# timer_main.net
KiCad netlist of a schematic drawn in Altium Designer
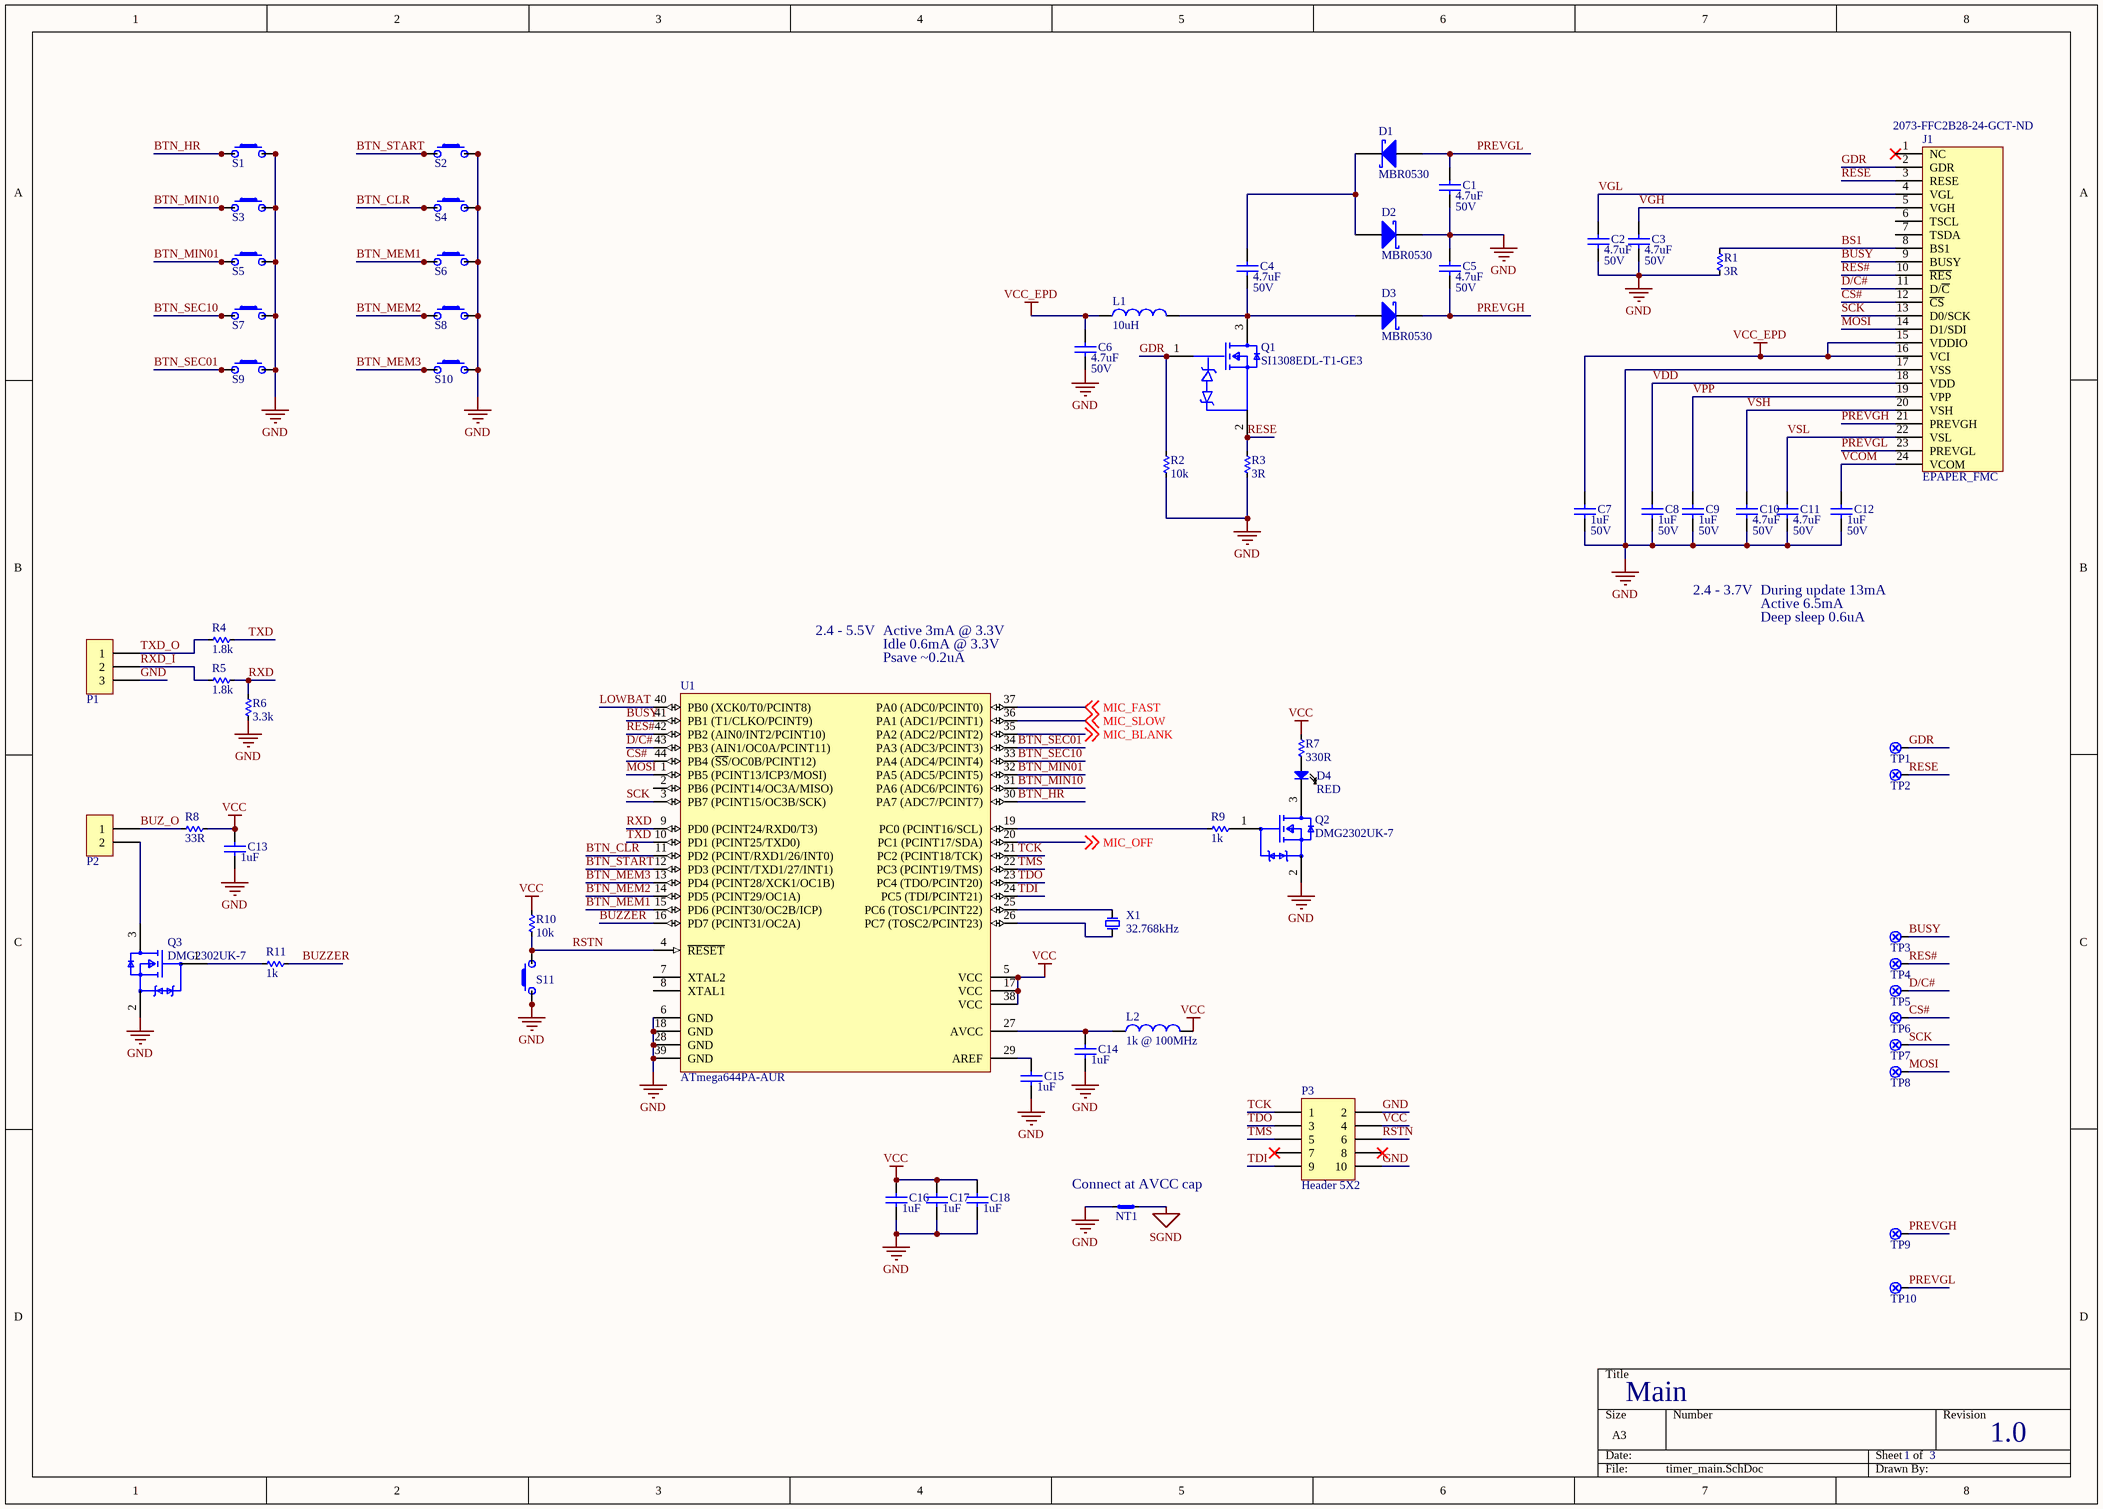
[diagram p0: timer_main.SchDoc]

(export (version "E")
  (design (tool "Eeschema 10.0.6"))
  (components
    (comp (ref "C1")
      (value "4.7uF")
      (footprint "C0805/2012")
      (description "Capacitor")
      (fields (field (name "TOLERANCE") "x%") (field (name "VOLTAGE") "50V") (field (name "Comment") "CAP"))
      (libsource (lib "ZMPlib") (part "CAP"))
    )
    (comp (ref "C2")
      (value "4.7uF")
      (footprint "C0805/2012")
      (description "Capacitor")
      (fields (field (name "TOLERANCE") "x%") (field (name "VOLTAGE") "50V") (field (name "Comment") "CAP"))
      (libsource (lib "ZMPlib") (part "CAP"))
    )
    (comp (ref "C3")
      (value "4.7uF")
      (footprint "C0805/2012")
      (description "Capacitor")
      (fields (field (name "TOLERANCE") "x%") (field (name "VOLTAGE") "50V") (field (name "Comment") "CAP"))
      (libsource (lib "ZMPlib") (part "CAP"))
    )
    (comp (ref "C4")
      (value "4.7uF")
      (footprint "C0805/2012")
      (description "Capacitor")
      (fields (field (name "TOLERANCE") "x%") (field (name "VOLTAGE") "50V") (field (name "Comment") "CAP"))
      (libsource (lib "ZMPlib") (part "CAP"))
    )
    (comp (ref "C5")
      (value "4.7uF")
      (footprint "C0805/2012")
      (description "Capacitor")
      (fields (field (name "TOLERANCE") "x%") (field (name "VOLTAGE") "50V") (field (name "Comment") "CAP"))
      (libsource (lib "ZMPlib") (part "CAP"))
    )
    (comp (ref "C6")
      (value "4.7uF")
      (footprint "C0805/2012")
      (description "Capacitor")
      (fields (field (name "TOLERANCE") "x%") (field (name "VOLTAGE") "50V") (field (name "Comment") "CAP"))
      (libsource (lib "ZMPlib") (part "CAP"))
    )
    (comp (ref "C7")
      (value "1uF")
      (footprint "C0603/1608")
      (description "Capacitor")
      (fields (field (name "TOLERANCE") "x%") (field (name "VOLTAGE") "50V") (field (name "Comment") "CAP"))
      (libsource (lib "ZMPlib") (part "CAP"))
    )
    (comp (ref "C8")
      (value "1uF")
      (footprint "C0603/1608")
      (description "Capacitor")
      (fields (field (name "TOLERANCE") "x%") (field (name "VOLTAGE") "50V") (field (name "Comment") "CAP"))
      (libsource (lib "ZMPlib") (part "CAP"))
    )
    (comp (ref "C9")
      (value "1uF")
      (footprint "C0603/1608")
      (description "Capacitor")
      (fields (field (name "TOLERANCE") "x%") (field (name "VOLTAGE") "50V") (field (name "Comment") "CAP"))
      (libsource (lib "ZMPlib") (part "CAP"))
    )
    (comp (ref "C10")
      (value "4.7uF")
      (footprint "C0805/2012")
      (description "Capacitor")
      (fields (field (name "TOLERANCE") "x%") (field (name "VOLTAGE") "50V") (field (name "Comment") "CAP"))
      (libsource (lib "ZMPlib") (part "CAP"))
    )
    (comp (ref "C11")
      (value "4.7uF")
      (footprint "C0805/2012")
      (description "Capacitor")
      (fields (field (name "TOLERANCE") "x%") (field (name "VOLTAGE") "50V") (field (name "Comment") "CAP"))
      (libsource (lib "ZMPlib") (part "CAP"))
    )
    (comp (ref "C12")
      (value "1uF")
      (footprint "C0603/1608")
      (description "Capacitor")
      (fields (field (name "TOLERANCE") "x%") (field (name "VOLTAGE") "50V") (field (name "Comment") "CAP"))
      (libsource (lib "ZMPlib") (part "CAP"))
    )
    (comp (ref "C13")
      (value "1uF")
      (footprint "C0603/1608")
      (description "Capacitor")
      (fields (field (name "TOLERANCE") "x%") (field (name "VOLTAGE") "6.3V"))
      (libsource (lib "ZMPlib") (part "CAP"))
    )
    (comp (ref "C14")
      (value "1uF")
      (footprint "C0603/1608")
      (description "Capacitor")
      (fields (field (name "TOLERANCE") "x%") (field (name "VOLTAGE") "6.3V"))
      (libsource (lib "ZMPlib") (part "CAP"))
    )
    (comp (ref "C15")
      (value "1uF")
      (footprint "C0603/1608")
      (description "Capacitor")
      (fields (field (name "TOLERANCE") "x%") (field (name "VOLTAGE") "6.3V"))
      (libsource (lib "ZMPlib") (part "CAP"))
    )
    (comp (ref "C16")
      (value "1uF")
      (footprint "C0603/1608")
      (description "Capacitor")
      (fields (field (name "TOLERANCE") "x%") (field (name "VOLTAGE") "6.3V"))
      (libsource (lib "ZMPlib") (part "CAP"))
    )
    (comp (ref "C17")
      (value "1uF")
      (footprint "C0603/1608")
      (description "Capacitor")
      (fields (field (name "TOLERANCE") "x%") (field (name "VOLTAGE") "6.3V"))
      (libsource (lib "ZMPlib") (part "CAP"))
    )
    (comp (ref "C18")
      (value "1uF")
      (footprint "C0603/1608")
      (description "Capacitor")
      (fields (field (name "TOLERANCE") "x%") (field (name "VOLTAGE") "6.3V"))
      (libsource (lib "ZMPlib") (part "CAP"))
    )
    (comp (ref "D1")
      (value "MBR0530")
      (footprint "FAIR-SOD123-2_V")
      (description "Diode Schottky 30V 0.5A 2-Pin SOD-123 T/R")
      (fields (field (name "MANUFACTURER") "Fairchild"))
      (libsource (lib "Altium Content Vault") (part "DSKY-AK-2"))
    )
    (comp (ref "D2")
      (value "MBR0530")
      (footprint "FAIR-SOD123-2_V")
      (description "Diode Schottky 30V 0.5A 2-Pin SOD-123 T/R")
      (fields (field (name "MANUFACTURER") "Fairchild"))
      (libsource (lib "Altium Content Vault") (part "DSKY-AK-2"))
    )
    (comp (ref "D3")
      (value "MBR0530")
      (footprint "FAIR-SOD123-2_V")
      (description "Diode Schottky 30V 0.5A 2-Pin SOD-123 T/R")
      (fields (field (name "MANUFACTURER") "Fairchild"))
      (libsource (lib "Altium Content Vault") (part "DSKY-AK-2"))
    )
    (comp (ref "D4")
      (value "RED")
      (footprint "0603/1608_P")
      (description "LED")
      (libsource (lib "ZMPlib") (part "LED"))
    )
    (comp (ref "J1")
      (value "EPAPER_FMC")
      (footprint "FFC2B28-24-G REV")
      (description "FMC connector for epaper display from Dailan Good Display")
      (fields (field (name "SUPPLIER PART NUMBER 1") "2073-FFC2B28-24-GCT-ND"))
      (libsource (lib "ZMPlib") (part "EPAPER_FMC"))
    )
    (comp (ref "L1")
      (value "10uH")
      (footprint "IND4x4mm")
      (description "Inductor")
      (fields (field (name "Comment") "IND"))
      (libsource (lib "ZMPlib") (part "IND"))
    )
    (comp (ref "L2")
      (value "1k @ 100MHz")
      (footprint "R0603/1608")
      (description "Inductor")
      (fields (field (name "Comment") "FERRITE"))
      (libsource (lib "ZMPlib") (part "IND"))
    )
    (comp (ref "NT1")
      (value "NET_TIE2")
      (footprint "NT2_0.5mm")
      (description "Link between nets")
      (libsource (lib "ZMPlib") (part "NET_TIE2"))
    )
    (comp (ref "P1")
      (value "SIL3")
      (footprint "PINS-3")
      (description "SIL package, 3 pins")
      (libsource (lib "ZMPlib") (part "SIL3"))
    )
    (comp (ref "P2")
      (value "SIL2")
      (footprint "PINS-2")
      (description "SIL package, 2 pins")
      (libsource (lib "ZMPlib") (part "SIL2"))
    )
    (comp (ref "P3")
      (value "Header 5X2")
      (footprint "HDR2X5")
      (description "Header, 5-Pin, Dual row")
      (fields (field (name "PUBLISHER") "Altium Limited"))
      (libsource (lib "Miscellaneous Connectors") (part "Header 5X2"))
    )
    (comp (ref "Q1")
      (value "SI1308EDL-T1-GE3")
      (footprint "FP-S-03946-MFG")
      (description "MOSFET N-CH 30V 1.4A SC-70-3")
      (fields
        (field (name "OCTOPART") "https://octopart.com/si1308edl-t1-ge3-vishay-45284459")
        (field (name "MANUFACTURER") "Vishay")
      )
      (libsource (lib "Altium Content Vault") (part "b3bb3e825a9d846c0de22584db20962"))
    )
    (comp (ref "Q2")
      (value "DMG2302UK-7")
      (footprint "FP-SOT23-MFG")
      (description "MOSFET N-CH 20V 2.8A SOT23")
      (fields
        (field (name "OCTOPART") "https://octopart.com/dmg2302uk-7-diodes+inc.-73850182")
        (field (name "MANUFACTURER") "Diodes Inc.")
      )
      (libsource (lib "Altium Content Vault") (part "87c0c04a04979492222792dd46c39c9"))
    )
    (comp (ref "Q3")
      (value "DMG2302UK-7")
      (footprint "FP-SOT23-MFG")
      (description "MOSFET N-CH 20V 2.8A SOT23")
      (fields
        (field (name "OCTOPART") "https://octopart.com/dmg2302uk-7-diodes+inc.-73850182")
        (field (name "MANUFACTURER") "Diodes Inc.")
      )
      (libsource (lib "Altium Content Vault") (part "87c0c04a04979492222792dd46c39c9"))
    )
    (comp (ref "R1")
      (value "3R")
      (footprint "R0603/1608")
      (description "Resistor")
      (fields (field (name "TOLERANCE") "x%") (field (name "Comment") "RES"))
      (libsource (lib "ZMPlib") (part "RES"))
    )
    (comp (ref "R2")
      (value "10k")
      (footprint "R0603/1608")
      (description "Resistor")
      (fields (field (name "TOLERANCE") "x%") (field (name "Comment") "RES"))
      (libsource (lib "ZMPlib") (part "RES"))
    )
    (comp (ref "R3")
      (value "3R")
      (footprint "R0603/1608")
      (description "Resistor")
      (fields (field (name "TOLERANCE") "x%") (field (name "Comment") "RES"))
      (libsource (lib "ZMPlib") (part "RES"))
    )
    (comp (ref "R4")
      (value "1.8k")
      (footprint "R0603/1608")
      (description "Resistor")
      (fields (field (name "TOLERANCE") "x%") (field (name "Comment") "RES"))
      (libsource (lib "ZMPlib") (part "RES"))
    )
    (comp (ref "R5")
      (value "1.8k")
      (footprint "R0603/1608")
      (description "Resistor")
      (fields (field (name "TOLERANCE") "x%") (field (name "Comment") "RES"))
      (libsource (lib "ZMPlib") (part "RES"))
    )
    (comp (ref "R6")
      (value "3.3k")
      (footprint "R0603/1608")
      (description "Resistor")
      (fields (field (name "TOLERANCE") "x%") (field (name "Comment") "RES"))
      (libsource (lib "ZMPlib") (part "RES"))
    )
    (comp (ref "R7")
      (value "330R")
      (footprint "R0603/1608")
      (description "Resistor")
      (fields (field (name "TOLERANCE") "x%") (field (name "Comment") "RES"))
      (libsource (lib "ZMPlib") (part "RES"))
    )
    (comp (ref "R8")
      (value "33R")
      (footprint "R0603/1608")
      (description "Resistor")
      (fields (field (name "TOLERANCE") "x%") (field (name "Comment") "RES"))
      (libsource (lib "ZMPlib") (part "RES"))
    )
    (comp (ref "R9")
      (value "1k")
      (footprint "R0603/1608")
      (description "Resistor")
      (fields (field (name "TOLERANCE") "x%") (field (name "Comment") "RES"))
      (libsource (lib "ZMPlib") (part "RES"))
    )
    (comp (ref "R10")
      (value "10k")
      (footprint "R0603/1608")
      (description "Resistor")
      (fields (field (name "TOLERANCE") "x%") (field (name "Comment") "RES"))
      (libsource (lib "ZMPlib") (part "RES"))
    )
    (comp (ref "R11")
      (value "1k")
      (footprint "R0603/1608")
      (description "Resistor")
      (fields (field (name "TOLERANCE") "x%") (field (name "Comment") "RES"))
      (libsource (lib "ZMPlib") (part "RES"))
    )
    (comp (ref "S1")
      (value "SW")
      (footprint "SW-PTS645-SMT")
      (description "Switch")
      (libsource (lib "ZMPlib") (part "SW-PB"))
    )
    (comp (ref "S2")
      (value "SW")
      (footprint "SW-PTS645-SMT")
      (description "Switch")
      (libsource (lib "ZMPlib") (part "SW-PB"))
    )
    (comp (ref "S3")
      (value "SW")
      (footprint "SW-PTS645-SMT")
      (description "Switch")
      (libsource (lib "ZMPlib") (part "SW-PB"))
    )
    (comp (ref "S4")
      (value "SW")
      (footprint "SW-PTS645-SMT")
      (description "Switch")
      (libsource (lib "ZMPlib") (part "SW-PB"))
    )
    (comp (ref "S5")
      (value "SW")
      (footprint "SW-PTS645-SMT")
      (description "Switch")
      (libsource (lib "ZMPlib") (part "SW-PB"))
    )
    (comp (ref "S6")
      (value "SW")
      (footprint "SW-PTS645-SMT")
      (description "Switch")
      (libsource (lib "ZMPlib") (part "SW-PB"))
    )
    (comp (ref "S7")
      (value "SW")
      (footprint "SW-PTS645-SMT")
      (description "Switch")
      (libsource (lib "ZMPlib") (part "SW-PB"))
    )
    (comp (ref "S8")
      (value "SW")
      (footprint "SW-PTS645-SMT")
      (description "Switch")
      (libsource (lib "ZMPlib") (part "SW-PB"))
    )
    (comp (ref "S9")
      (value "SW")
      (footprint "SW-PTS645-SMT")
      (description "Switch")
      (libsource (lib "ZMPlib") (part "SW-PB"))
    )
    (comp (ref "S10")
      (value "SW")
      (footprint "SW-PTS645-SMT")
      (description "Switch")
      (libsource (lib "ZMPlib") (part "SW-PB"))
    )
    (comp (ref "S11")
      (value "SW")
      (footprint "SW-PTS645-SMT")
      (description "Switch")
      (libsource (lib "ZMPlib") (part "SW-PB"))
    )
    (comp (ref "TP1")
      (value "TP")
      (footprint "TP-1.0")
      (description "Test point")
      (libsource (lib "ZMPlib") (part "TP"))
    )
    (comp (ref "TP2")
      (value "TP")
      (footprint "TP-1.0")
      (description "Test point")
      (libsource (lib "ZMPlib") (part "TP"))
    )
    (comp (ref "TP3")
      (value "TP")
      (footprint "TP-1.0")
      (description "Test point")
      (libsource (lib "ZMPlib") (part "TP"))
    )
    (comp (ref "TP4")
      (value "TP")
      (footprint "TP-1.0")
      (description "Test point")
      (libsource (lib "ZMPlib") (part "TP"))
    )
    (comp (ref "TP5")
      (value "TP")
      (footprint "TP-1.0")
      (description "Test point")
      (libsource (lib "ZMPlib") (part "TP"))
    )
    (comp (ref "TP6")
      (value "TP")
      (footprint "TP-1.0")
      (description "Test point")
      (libsource (lib "ZMPlib") (part "TP"))
    )
    (comp (ref "TP7")
      (value "TP")
      (footprint "TP-1.0")
      (description "Test point")
      (libsource (lib "ZMPlib") (part "TP"))
    )
    (comp (ref "TP8")
      (value "TP")
      (footprint "TP-1.0")
      (description "Test point")
      (libsource (lib "ZMPlib") (part "TP"))
    )
    (comp (ref "TP9")
      (value "TP")
      (footprint "TP-1.0")
      (description "Test point")
      (libsource (lib "ZMPlib") (part "TP"))
    )
    (comp (ref "TP10")
      (value "TP")
      (footprint "TP-1.0")
      (description "Test point")
      (libsource (lib "ZMPlib") (part "TP"))
    )
    (comp (ref "U1")
      (value "ATmega644PA-AUR")
      (footprint "44A_N")
      (libsource (lib "Altium Content Vault") (part "MC-8B-ATM128-SQ44"))
    )
    (comp (ref "X1")
      (value "32.768kHz")
      (footprint "CMR200T")
      (description "Crystal")
      (fields (field (name "Comment") "XTAL"))
      (libsource (lib "ZMPlib") (part "XTAL"))
    )
  )
  (nets
    (net (code "1") (name "/BS1") (class "Default")
      (node (ref "J1") (pin "8") (pinfunction "BS1_8") (pintype "passive"))
      (node (ref "R1") (pin "1") (pinfunction "1_1") (pintype "passive"))
    )
    (net (code "2") (name "/BTN_CLR") (class "Default")
      (node (ref "S4") (pin "1") (pinfunction "1_1") (pintype "passive"))
      (node (ref "S4") (pin "2") (pinfunction "2_2") (pintype "passive"))
      (node (ref "U1") (pin "11") (pinfunction "PD2_(PCINT/RXD1/26/INT0)_11") (pintype "bidirectional"))
    )
    (net (code "3") (name "/BTN_HR") (class "Default")
      (node (ref "S1") (pin "1") (pinfunction "1_1") (pintype "passive"))
      (node (ref "S1") (pin "2") (pinfunction "2_2") (pintype "passive"))
      (node (ref "U1") (pin "30") (pinfunction "PA7_(ADC7/PCINT7)_30") (pintype "bidirectional"))
    )
    (net (code "4") (name "/BTN_MEM1") (class "Default")
      (node (ref "S6") (pin "1") (pinfunction "1_1") (pintype "passive"))
      (node (ref "S6") (pin "2") (pinfunction "2_2") (pintype "passive"))
      (node (ref "U1") (pin "15") (pinfunction "PD6_(PCINT30/OC2B/ICP)_15") (pintype "bidirectional"))
    )
    (net (code "5") (name "/BTN_MEM2") (class "Default")
      (node (ref "S8") (pin "1") (pinfunction "1_1") (pintype "passive"))
      (node (ref "S8") (pin "2") (pinfunction "2_2") (pintype "passive"))
      (node (ref "U1") (pin "14") (pinfunction "PD5_(PCINT29/OC1A)_14") (pintype "bidirectional"))
    )
    (net (code "6") (name "/BTN_MEM3") (class "Default")
      (node (ref "S10") (pin "1") (pinfunction "1_1") (pintype "passive"))
      (node (ref "S10") (pin "2") (pinfunction "2_2") (pintype "passive"))
      (node (ref "U1") (pin "13") (pinfunction "PD4_(PCINT28/XCK1/OC1B)_13") (pintype "bidirectional"))
    )
    (net (code "7") (name "/BTN_MIN01") (class "Default")
      (node (ref "S5") (pin "1") (pinfunction "1_1") (pintype "passive"))
      (node (ref "S5") (pin "2") (pinfunction "2_2") (pintype "passive"))
      (node (ref "U1") (pin "32") (pinfunction "PA5_(ADC5/PCINT5)_32") (pintype "bidirectional"))
    )
    (net (code "8") (name "/BTN_MIN10") (class "Default")
      (node (ref "S3") (pin "1") (pinfunction "1_1") (pintype "passive"))
      (node (ref "S3") (pin "2") (pinfunction "2_2") (pintype "passive"))
      (node (ref "U1") (pin "31") (pinfunction "PA6_(ADC6/PCINT6)_31") (pintype "bidirectional"))
    )
    (net (code "9") (name "/BTN_SEC01") (class "Default")
      (node (ref "S9") (pin "1") (pinfunction "1_1") (pintype "passive"))
      (node (ref "S9") (pin "2") (pinfunction "2_2") (pintype "passive"))
      (node (ref "U1") (pin "34") (pinfunction "PA3_(ADC3/PCINT3)_34") (pintype "bidirectional"))
    )
    (net (code "10") (name "/BTN_SEC10") (class "Default")
      (node (ref "S7") (pin "1") (pinfunction "1_1") (pintype "passive"))
      (node (ref "S7") (pin "2") (pinfunction "2_2") (pintype "passive"))
      (node (ref "U1") (pin "33") (pinfunction "PA4_(ADC4/PCINT4)_33") (pintype "bidirectional"))
    )
    (net (code "11") (name "/BTN_START") (class "Default")
      (node (ref "S2") (pin "1") (pinfunction "1_1") (pintype "passive"))
      (node (ref "S2") (pin "2") (pinfunction "2_2") (pintype "passive"))
      (node (ref "U1") (pin "12") (pinfunction "PD3_(PCINT/TXD1/27/INT1)_12") (pintype "bidirectional"))
    )
    (net (code "12") (name "/BUSY") (class "Default")
      (node (ref "J1") (pin "9") (pinfunction "BUSY_9") (pintype "passive"))
      (node (ref "TP3") (pin "0") (pinfunction "0_0") (pintype "passive"))
      (node (ref "U1") (pin "41") (pinfunction "PB1_(T1/CLKO/PCINT9)_41") (pintype "bidirectional"))
    )
    (net (code "13") (name "/BUZZER") (class "Default")
      (node (ref "R11") (pin "2") (pinfunction "2_2") (pintype "passive"))
      (node (ref "U1") (pin "16") (pinfunction "PD7_(PCINT31/OC2A)_16") (pintype "bidirectional"))
    )
    (net (code "14") (name "/BUZ_O") (class "Default")
      (node (ref "P2") (pin "1") (pinfunction "1_1") (pintype "passive"))
      (node (ref "R8") (pin "1") (pinfunction "1_1") (pintype "passive"))
    )
    (net (code "15") (name "/CS#") (class "Default")
      (node (ref "J1") (pin "12") (pinfunction "~{CS}_12") (pintype "passive"))
      (node (ref "TP6") (pin "0") (pinfunction "0_0") (pintype "passive"))
      (node (ref "U1") (pin "44") (pinfunction "PB4_(~{SS}/OC0B/PCINT12)_44") (pintype "bidirectional"))
    )
    (net (code "16") (name "/D{slash}C#") (class "Default")
      (node (ref "J1") (pin "11") (pinfunction "D/~{C}_11") (pintype "passive"))
      (node (ref "TP5") (pin "0") (pinfunction "0_0") (pintype "passive"))
      (node (ref "U1") (pin "43") (pinfunction "PB3_(AIN1/OC0A/PCINT11)_43") (pintype "bidirectional"))
    )
    (net (code "17") (name "/GDR") (class "Default")
      (node (ref "J1") (pin "2") (pinfunction "GDR_2") (pintype "passive"))
      (node (ref "Q1") (pin "1") (pinfunction "G_1") (pintype "passive"))
      (node (ref "R2") (pin "1") (pinfunction "1_1") (pintype "passive"))
      (node (ref "TP1") (pin "0") (pinfunction "0_0") (pintype "passive"))
    )
    (net (code "18") (name "/LOWBAT") (class "Default")
      (node (ref "U1") (pin "40") (pinfunction "PB0_(XCK0/T0/PCINT8)_40") (pintype "bidirectional"))
    )
    (net (code "19") (name "/MOSI") (class "Default")
      (node (ref "J1") (pin "14") (pinfunction "D1/SDI_14") (pintype "passive"))
      (node (ref "TP8") (pin "0") (pinfunction "0_0") (pintype "passive"))
      (node (ref "U1") (pin "1") (pinfunction "PB5_(PCINT13/ICP3/MOSI)_1") (pintype "bidirectional"))
    )
    (net (code "20") (name "/PREVGH") (class "Default")
      (node (ref "C5") (pin "1") (pinfunction "1_1") (pintype "passive"))
      (node (ref "D3") (pin "2") (pinfunction "K_2") (pintype "passive"))
      (node (ref "J1") (pin "21") (pinfunction "PREVGH_21") (pintype "passive"))
      (node (ref "TP9") (pin "0") (pinfunction "0_0") (pintype "passive"))
    )
    (net (code "21") (name "/PREVGL") (class "Default")
      (node (ref "C1") (pin "2") (pinfunction "2_2") (pintype "passive"))
      (node (ref "D1") (pin "1") (pinfunction "A_1") (pintype "passive"))
      (node (ref "J1") (pin "23") (pinfunction "PREVGL_23") (pintype "passive"))
      (node (ref "TP10") (pin "0") (pinfunction "0_0") (pintype "passive"))
    )
    (net (code "22") (name "/RES#") (class "Default")
      (node (ref "J1") (pin "10") (pinfunction "~{RES}_10") (pintype "passive"))
      (node (ref "TP4") (pin "0") (pinfunction "0_0") (pintype "passive"))
      (node (ref "U1") (pin "42") (pinfunction "PB2_(AIN0/INT2/PCINT10)_42") (pintype "bidirectional"))
    )
    (net (code "23") (name "/RESE") (class "Default")
      (node (ref "J1") (pin "3") (pinfunction "RESE_3") (pintype "passive"))
      (node (ref "Q1") (pin "2") (pinfunction "S_2") (pintype "passive"))
      (node (ref "R3") (pin "1") (pinfunction "1_1") (pintype "passive"))
      (node (ref "TP2") (pin "0") (pinfunction "0_0") (pintype "passive"))
    )
    (net (code "24") (name "/RSTN") (class "Default")
      (node (ref "P3") (pin "6") (pinfunction "6_6") (pintype "passive"))
      (node (ref "R10") (pin "2") (pinfunction "2_2") (pintype "passive"))
      (node (ref "S11") (pin "3") (pinfunction "3_3") (pintype "passive"))
      (node (ref "S11") (pin "4") (pinfunction "4_4") (pintype "passive"))
      (node (ref "U1") (pin "4") (pinfunction "~{RESET}_4") (pintype "input"))
    )
    (net (code "25") (name "/RXD") (class "Default")
      (node (ref "R5") (pin "2") (pinfunction "2_2") (pintype "passive"))
      (node (ref "R6") (pin "1") (pinfunction "1_1") (pintype "passive"))
      (node (ref "U1") (pin "9") (pinfunction "PD0_(PCINT24/RXD0/T3)_9") (pintype "bidirectional"))
    )
    (net (code "26") (name "/RXD_I") (class "Default")
      (node (ref "P1") (pin "2") (pinfunction "2_2") (pintype "passive"))
      (node (ref "R5") (pin "1") (pinfunction "1_1") (pintype "passive"))
    )
    (net (code "27") (name "/SCK") (class "Default")
      (node (ref "J1") (pin "13") (pinfunction "D0/SCK_13") (pintype "passive"))
      (node (ref "TP7") (pin "0") (pinfunction "0_0") (pintype "passive"))
      (node (ref "U1") (pin "3") (pinfunction "PB7_(PCINT15/OC3B/SCK)_3") (pintype "bidirectional"))
    )
    (net (code "28") (name "/TCK") (class "Default")
      (node (ref "P3") (pin "1") (pinfunction "1_1") (pintype "passive"))
      (node (ref "U1") (pin "21") (pinfunction "PC2_(PCINT18/TCK)_21") (pintype "bidirectional"))
    )
    (net (code "29") (name "/TDI") (class "Default")
      (node (ref "P3") (pin "9") (pinfunction "9_9") (pintype "passive"))
      (node (ref "U1") (pin "24") (pinfunction "PC5_(TDI/PCINT21)_24") (pintype "bidirectional"))
    )
    (net (code "30") (name "/TDO") (class "Default")
      (node (ref "P3") (pin "3") (pinfunction "3_3") (pintype "passive"))
      (node (ref "U1") (pin "23") (pinfunction "PC4_(TDO/PCINT20)_23") (pintype "bidirectional"))
    )
    (net (code "31") (name "/TMS") (class "Default")
      (node (ref "P3") (pin "5") (pinfunction "5_5") (pintype "passive"))
      (node (ref "U1") (pin "22") (pinfunction "PC3_(PCINT19/TMS)_22") (pintype "bidirectional"))
    )
    (net (code "32") (name "/TXD") (class "Default")
      (node (ref "R4") (pin "2") (pinfunction "2_2") (pintype "passive"))
      (node (ref "U1") (pin "10") (pinfunction "PD1_(PCINT25/TXD0)_10") (pintype "bidirectional"))
    )
    (net (code "33") (name "/TXD_O") (class "Default")
      (node (ref "P1") (pin "1") (pinfunction "1_1") (pintype "passive"))
      (node (ref "R4") (pin "1") (pinfunction "1_1") (pintype "passive"))
    )
    (net (code "34") (name "/VCOM") (class "Default")
      (node (ref "C12") (pin "2") (pinfunction "2_2") (pintype "passive"))
      (node (ref "J1") (pin "24") (pinfunction "VCOM_24") (pintype "passive"))
    )
    (net (code "35") (name "/VDD") (class "Default")
      (node (ref "C8") (pin "2") (pinfunction "2_2") (pintype "passive"))
      (node (ref "J1") (pin "18") (pinfunction "VDD_18") (pintype "passive"))
    )
    (net (code "36") (name "/VGH") (class "Default")
      (node (ref "C3") (pin "2") (pinfunction "2_2") (pintype "passive"))
      (node (ref "J1") (pin "5") (pinfunction "VGH_5") (pintype "passive"))
    )
    (net (code "37") (name "/VGL") (class "Default")
      (node (ref "C2") (pin "2") (pinfunction "2_2") (pintype "passive"))
      (node (ref "J1") (pin "4") (pinfunction "VGL_4") (pintype "passive"))
    )
    (net (code "38") (name "/VPP") (class "Default")
      (node (ref "C9") (pin "2") (pinfunction "2_2") (pintype "passive"))
      (node (ref "J1") (pin "19") (pinfunction "VPP_19") (pintype "passive"))
    )
    (net (code "39") (name "/VSH") (class "Default")
      (node (ref "C10") (pin "2") (pinfunction "2_2") (pintype "passive"))
      (node (ref "J1") (pin "20") (pinfunction "VSH_20") (pintype "passive"))
    )
    (net (code "40") (name "/VSL") (class "Default")
      (node (ref "C11") (pin "2") (pinfunction "2_2") (pintype "passive"))
      (node (ref "J1") (pin "22") (pinfunction "VSL_22") (pintype "passive"))
    )
    (net (code "41") (name "GND") (class "Default")
      (node (ref "C1") (pin "1") (pinfunction "1_1") (pintype "passive"))
      (node (ref "C10") (pin "1") (pinfunction "1_1") (pintype "passive"))
      (node (ref "C11") (pin "1") (pinfunction "1_1") (pintype "passive"))
      (node (ref "C12") (pin "1") (pinfunction "1_1") (pintype "passive"))
      (node (ref "C13") (pin "1") (pinfunction "1_1") (pintype "passive"))
      (node (ref "C14") (pin "1") (pinfunction "1_1") (pintype "passive"))
      (node (ref "C15") (pin "1") (pinfunction "1_1") (pintype "passive"))
      (node (ref "C16") (pin "1") (pinfunction "1_1") (pintype "passive"))
      (node (ref "C17") (pin "1") (pinfunction "1_1") (pintype "passive"))
      (node (ref "C18") (pin "1") (pinfunction "1_1") (pintype "passive"))
      (node (ref "C2") (pin "1") (pinfunction "1_1") (pintype "passive"))
      (node (ref "C3") (pin "1") (pinfunction "1_1") (pintype "passive"))
      (node (ref "C5") (pin "2") (pinfunction "2_2") (pintype "passive"))
      (node (ref "C6") (pin "1") (pinfunction "1_1") (pintype "passive"))
      (node (ref "C7") (pin "1") (pinfunction "1_1") (pintype "passive"))
      (node (ref "C8") (pin "1") (pinfunction "1_1") (pintype "passive"))
      (node (ref "C9") (pin "1") (pinfunction "1_1") (pintype "passive"))
      (node (ref "D2") (pin "2") (pinfunction "K_2") (pintype "passive"))
      (node (ref "J1") (pin "17") (pinfunction "VSS_17") (pintype "passive"))
      (node (ref "NT1") (pin "1") (pinfunction "1_1") (pintype "passive"))
      (node (ref "P1") (pin "3") (pinfunction "3_3") (pintype "passive"))
      (node (ref "P3") (pin "10") (pinfunction "10_10") (pintype "passive"))
      (node (ref "P3") (pin "2") (pinfunction "2_2") (pintype "passive"))
      (node (ref "Q2") (pin "2") (pinfunction "S_2") (pintype "passive"))
      (node (ref "Q3") (pin "2") (pinfunction "S_2") (pintype "passive"))
      (node (ref "R1") (pin "2") (pinfunction "2_2") (pintype "passive"))
      (node (ref "R2") (pin "2") (pinfunction "2_2") (pintype "passive"))
      (node (ref "R3") (pin "2") (pinfunction "2_2") (pintype "passive"))
      (node (ref "R6") (pin "2") (pinfunction "2_2") (pintype "passive"))
      (node (ref "S1") (pin "3") (pinfunction "3_3") (pintype "passive"))
      (node (ref "S1") (pin "4") (pinfunction "4_4") (pintype "passive"))
      (node (ref "S10") (pin "3") (pinfunction "3_3") (pintype "passive"))
      (node (ref "S10") (pin "4") (pinfunction "4_4") (pintype "passive"))
      (node (ref "S11") (pin "1") (pinfunction "1_1") (pintype "passive"))
      (node (ref "S11") (pin "2") (pinfunction "2_2") (pintype "passive"))
      (node (ref "S2") (pin "3") (pinfunction "3_3") (pintype "passive"))
      (node (ref "S2") (pin "4") (pinfunction "4_4") (pintype "passive"))
      (node (ref "S3") (pin "3") (pinfunction "3_3") (pintype "passive"))
      (node (ref "S3") (pin "4") (pinfunction "4_4") (pintype "passive"))
      (node (ref "S4") (pin "3") (pinfunction "3_3") (pintype "passive"))
      (node (ref "S4") (pin "4") (pinfunction "4_4") (pintype "passive"))
      (node (ref "S5") (pin "3") (pinfunction "3_3") (pintype "passive"))
      (node (ref "S5") (pin "4") (pinfunction "4_4") (pintype "passive"))
      (node (ref "S6") (pin "3") (pinfunction "3_3") (pintype "passive"))
      (node (ref "S6") (pin "4") (pinfunction "4_4") (pintype "passive"))
      (node (ref "S7") (pin "3") (pinfunction "3_3") (pintype "passive"))
      (node (ref "S7") (pin "4") (pinfunction "4_4") (pintype "passive"))
      (node (ref "S8") (pin "3") (pinfunction "3_3") (pintype "passive"))
      (node (ref "S8") (pin "4") (pinfunction "4_4") (pintype "passive"))
      (node (ref "S9") (pin "3") (pinfunction "3_3") (pintype "passive"))
      (node (ref "S9") (pin "4") (pinfunction "4_4") (pintype "passive"))
      (node (ref "U1") (pin "18") (pinfunction "GND_18") (pintype "power_in"))
      (node (ref "U1") (pin "28") (pinfunction "GND_28") (pintype "power_in"))
      (node (ref "U1") (pin "39") (pinfunction "GND_39") (pintype "power_in"))
      (node (ref "U1") (pin "6") (pinfunction "GND_6") (pintype "power_in"))
    )
    (net (code "42") (name "MIC_BLANK") (class "Default")
      (node (ref "U1") (pin "35") (pinfunction "PA2_(ADC2/PCINT2)_35") (pintype "bidirectional"))
    )
    (net (code "43") (name "MIC_FAST") (class "Default")
      (node (ref "U1") (pin "37") (pinfunction "PA0_(ADC0/PCINT0)_37") (pintype "bidirectional"))
    )
    (net (code "44") (name "MIC_OFF") (class "Default")
      (node (ref "U1") (pin "20") (pinfunction "PC1_(PCINT17/SDA)_20") (pintype "bidirectional"))
    )
    (net (code "45") (name "MIC_SLOW") (class "Default")
      (node (ref "U1") (pin "36") (pinfunction "PA1_(ADC1/PCINT1)_36") (pintype "bidirectional"))
    )
    (net (code "46") (name "Net-(D1-K)") (class "Default")
      (node (ref "C4") (pin "2") (pinfunction "2_2") (pintype "passive"))
      (node (ref "D1") (pin "2") (pinfunction "K_2") (pintype "passive"))
      (node (ref "D2") (pin "1") (pinfunction "A_1") (pintype "passive"))
    )
    (net (code "47") (name "Net-(D3-A)") (class "Default")
      (node (ref "C4") (pin "1") (pinfunction "1_1") (pintype "passive"))
      (node (ref "D3") (pin "1") (pinfunction "A_1") (pintype "passive"))
      (node (ref "L1") (pin "2") (pinfunction "2_2") (pintype "passive"))
      (node (ref "Q1") (pin "3") (pinfunction "D_3") (pintype "passive"))
    )
    (net (code "48") (name "Net-(D4-Pad1)") (class "Default")
      (node (ref "D4") (pin "1") (pinfunction "1_1") (pintype "passive"))
      (node (ref "R7") (pin "2") (pinfunction "2_2") (pintype "passive"))
    )
    (net (code "49") (name "Net-(Q2-D)") (class "Default")
      (node (ref "D4") (pin "2") (pinfunction "2_2") (pintype "passive"))
      (node (ref "Q2") (pin "3") (pinfunction "D_3") (pintype "passive"))
    )
    (net (code "50") (name "Net-(Q2-G)") (class "Default")
      (node (ref "Q2") (pin "1") (pinfunction "G_1") (pintype "passive"))
      (node (ref "R9") (pin "2") (pinfunction "2_2") (pintype "passive"))
    )
    (net (code "51") (name "Net-(Q3-D)") (class "Default")
      (node (ref "P2") (pin "2") (pinfunction "2_2") (pintype "passive"))
      (node (ref "Q3") (pin "3") (pinfunction "D_3") (pintype "passive"))
    )
    (net (code "52") (name "Net-(Q3-G)") (class "Default")
      (node (ref "Q3") (pin "1") (pinfunction "G_1") (pintype "passive"))
      (node (ref "R11") (pin "1") (pinfunction "1_1") (pintype "passive"))
    )
    (net (code "53") (name "Net-(U1-AREF)") (class "Default")
      (node (ref "C15") (pin "2") (pinfunction "2_2") (pintype "passive"))
      (node (ref "U1") (pin "29") (pinfunction "AREF_29") (pintype "power_in"))
    )
    (net (code "54") (name "Net-(U1-AVCC)") (class "Default")
      (node (ref "C14") (pin "2") (pinfunction "2_2") (pintype "passive"))
      (node (ref "L2") (pin "1") (pinfunction "1_1") (pintype "passive"))
      (node (ref "U1") (pin "27") (pinfunction "AVCC_27") (pintype "power_in"))
    )
    (net (code "55") (name "Net-(U1-PC0_(PCINT16{slash}SCL))") (class "Default")
      (node (ref "R9") (pin "1") (pinfunction "1_1") (pintype "passive"))
      (node (ref "U1") (pin "19") (pinfunction "PC0_(PCINT16/SCL)_19") (pintype "bidirectional"))
    )
    (net (code "56") (name "Net-(U1-PC6_(TOSC1{slash}PCINT22))") (class "Default")
      (node (ref "U1") (pin "25") (pinfunction "PC6_(TOSC1/PCINT22)_25") (pintype "bidirectional"))
      (node (ref "X1") (pin "2") (pinfunction "2_2") (pintype "passive"))
    )
    (net (code "57") (name "Net-(U1-PC7_(TOSC2{slash}PCINT23))") (class "Default")
      (node (ref "U1") (pin "26") (pinfunction "PC7_(TOSC2/PCINT23)_26") (pintype "bidirectional"))
      (node (ref "X1") (pin "1") (pinfunction "1_1") (pintype "passive"))
    )
    (net (code "58") (name "SGND") (class "Default")
      (node (ref "NT1") (pin "2") (pinfunction "2_2") (pintype "passive"))
    )
    (net (code "59") (name "VCC") (class "Default")
      (node (ref "C13") (pin "2") (pinfunction "2_2") (pintype "passive"))
      (node (ref "C16") (pin "2") (pinfunction "2_2") (pintype "passive"))
      (node (ref "C17") (pin "2") (pinfunction "2_2") (pintype "passive"))
      (node (ref "C18") (pin "2") (pinfunction "2_2") (pintype "passive"))
      (node (ref "L2") (pin "2") (pinfunction "2_2") (pintype "passive"))
      (node (ref "P3") (pin "4") (pinfunction "4_4") (pintype "passive"))
      (node (ref "R10") (pin "1") (pinfunction "1_1") (pintype "passive"))
      (node (ref "R7") (pin "1") (pinfunction "1_1") (pintype "passive"))
      (node (ref "R8") (pin "2") (pinfunction "2_2") (pintype "passive"))
      (node (ref "U1") (pin "17") (pinfunction "VCC_17") (pintype "power_in"))
      (node (ref "U1") (pin "38") (pinfunction "VCC_38") (pintype "power_in"))
      (node (ref "U1") (pin "5") (pinfunction "VCC_5") (pintype "power_in"))
    )
    (net (code "60") (name "VCC_EPD") (class "Default")
      (node (ref "C6") (pin "2") (pinfunction "2_2") (pintype "passive"))
      (node (ref "C7") (pin "2") (pinfunction "2_2") (pintype "passive"))
      (node (ref "J1") (pin "15") (pinfunction "VDDIO_15") (pintype "passive"))
      (node (ref "J1") (pin "16") (pinfunction "VCI_16") (pintype "passive"))
      (node (ref "L1") (pin "1") (pinfunction "1_1") (pintype "passive"))
    )
    (net (code "61") (name "unconnected-(J1-NC-Pad1)") (class "Default")
      (node (ref "J1") (pin "1") (pinfunction "NC_1") (pintype "passive+no_connect"))
    )
    (net (code "62") (name "unconnected-(J1-TSCL-Pad6)") (class "Default")
      (node (ref "J1") (pin "6") (pinfunction "TSCL_6") (pintype "passive"))
    )
    (net (code "63") (name "unconnected-(J1-TSDA-Pad7)") (class "Default")
      (node (ref "J1") (pin "7") (pinfunction "TSDA_7") (pintype "passive"))
    )
    (net (code "64") (name "unconnected-(P3-Pad7)") (class "Default")
      (node (ref "P3") (pin "7") (pinfunction "7_7") (pintype "passive+no_connect"))
    )
    (net (code "65") (name "unconnected-(P3-Pad8)") (class "Default")
      (node (ref "P3") (pin "8") (pinfunction "8_8") (pintype "passive+no_connect"))
    )
    (net (code "66") (name "unconnected-(U1-PB6_(PCINT14{slash}OC3A{slash}MISO)-Pad2)") (class "Default")
      (node (ref "U1") (pin "2") (pinfunction "PB6_(PCINT14/OC3A/MISO)_2") (pintype "bidirectional"))
    )
    (net (code "67") (name "unconnected-(U1-XTAL1-Pad8)") (class "Default")
      (node (ref "U1") (pin "8") (pinfunction "XTAL1_8") (pintype "passive"))
    )
    (net (code "68") (name "unconnected-(U1-XTAL2-Pad7)") (class "Default")
      (node (ref "U1") (pin "7") (pinfunction "XTAL2_7") (pintype "passive"))
    )
  )
)
